# OLED_0_96-inch_Sch.net
KiCad netlist of a schematic drawn in Altium Designer
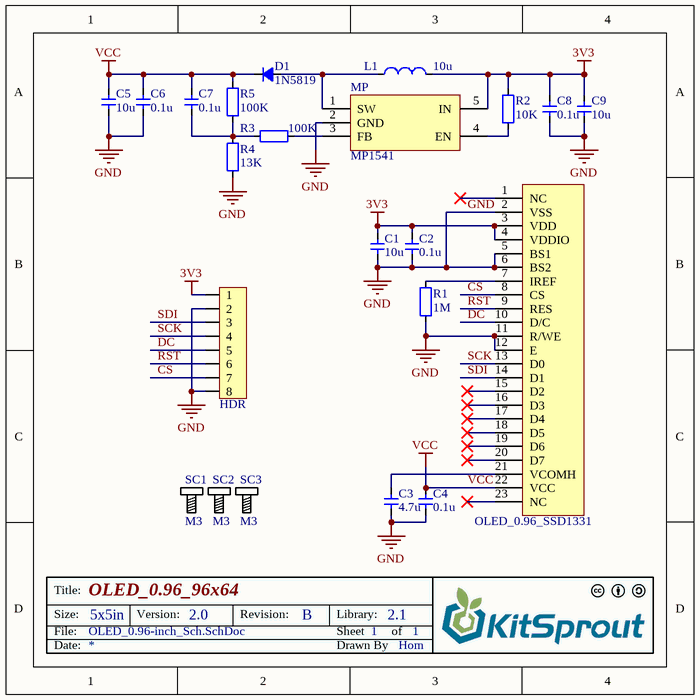
[diagram p0: OLED_0.96-inch_Sch.SchDoc]

(export (version "E")
  (design (tool "Eeschema 10.0.6"))
  (components
    (comp (ref "C1")
      (value "10u")
      (footprint "PCB_PassiveCap:CAP_0805")
      (description "Capacitor")
      (fields (field (name "Comment") "Cap_0805"))
      (libsource (lib "SCH_Passive") (part "Cap_0805"))
    )
    (comp (ref "C2")
      (value "0.1u")
      (footprint "PCB_PassiveCap:CAP_0805")
      (description "Capacitor")
      (fields (field (name "Comment") "Cap_0805"))
      (libsource (lib "SCH_Passive") (part "Cap_0805"))
    )
    (comp (ref "C3")
      (value "4.7u")
      (footprint "PCB_PassiveCap:CAP_0805")
      (description "Capacitor")
      (fields (field (name "Comment") "Cap_0805"))
      (libsource (lib "SCH_Passive") (part "Cap_0805"))
    )
    (comp (ref "C4")
      (value "0.1u")
      (footprint "PCB_PassiveCap:CAP_0805")
      (description "Capacitor")
      (fields (field (name "Comment") "Cap_0805"))
      (libsource (lib "SCH_Passive") (part "Cap_0805"))
    )
    (comp (ref "C5")
      (value "10u")
      (footprint "PCB_PassiveCap:CAP_0805")
      (description "Capacitor")
      (fields (field (name "Comment") "Cap_0805"))
      (libsource (lib "SCH_Passive") (part "Cap_0805"))
    )
    (comp (ref "C6")
      (value "0.1u")
      (footprint "PCB_PassiveCap:CAP_0805")
      (description "Capacitor")
      (fields (field (name "Comment") "Cap_0805"))
      (libsource (lib "SCH_Passive") (part "Cap_0805"))
    )
    (comp (ref "C7")
      (value "0.1u")
      (footprint "PCB_PassiveCap:CAP_0805")
      (description "Capacitor")
      (fields (field (name "Comment") "Cap_0805"))
      (libsource (lib "SCH_Passive") (part "Cap_0805"))
    )
    (comp (ref "C8")
      (value "0.1u")
      (footprint "PCB_PassiveCap:CAP_0805")
      (description "Capacitor")
      (fields (field (name "Comment") "Cap_0805"))
      (libsource (lib "SCH_Passive") (part "Cap_0805"))
    )
    (comp (ref "C9")
      (value "10u")
      (footprint "PCB_PassiveCap:CAP_0805")
      (description "Capacitor")
      (fields (field (name "Comment") "Cap_0805"))
      (libsource (lib "SCH_Passive") (part "Cap_0805"))
    )
    (comp (ref "D1")
      (value "1N5819")
      (footprint "PCB_ActiveDIO:DO-214AC")
      (description "Diode")
      (fields (field (name "Comment") "Diode_SMA"))
      (libsource (lib "SCH_Active") (part "Diode_SMA"))
    )
    (comp (ref "HDR")
      (value "HDR1x8_1.27")
      (footprint "PCB_ConnectorHDR:HDR1X8_1.27_180")
      (description "Header")
      (libsource (lib "SCH_ConnectorHDR") (part "HDR1x8_1.27"))
    )
    (comp (ref "L1")
      (value "10u")
      (footprint "PCB_PassiveInd:IND_CD32")
      (description "Inductor")
      (fields (field (name "Comment") "Ind_CD32"))
      (libsource (lib "SCH_Passive") (part "Ind_CD32"))
    )
    (comp (ref "MP")
      (value "MP1541")
      (footprint "PCB_IntegratedCircuit:SOT23-5")
      (description "Boost")
      (libsource (lib "SCH_IntegratedCircuit") (part "MP1541"))
    )
    (comp (ref "OLED_0.96_SSD1331")
      (value "OLED_0.96_SSD1331")
      (footprint "PCB_Module:OLED_0.96_96x64_SSD1331")
      (description "OLED")
      (libsource (lib "SCH_Module") (part "OLED_0.96_SSD1331"))
    )
    (comp (ref "R1")
      (value "1M")
      (footprint "PCB_PassiveRes:RES_0603")
      (description "Resistor")
      (fields (field (name "Comment") "Res_0603"))
      (libsource (lib "SCH_Passive") (part "Res_0603"))
    )
    (comp (ref "R2")
      (value "10K")
      (footprint "PCB_PassiveRes:RES_0603")
      (description "Resistor")
      (fields (field (name "Comment") "Res_0603"))
      (libsource (lib "SCH_Passive") (part "Res_0603"))
    )
    (comp (ref "R3")
      (value "100K")
      (footprint "PCB_PassiveRes:RES_0603")
      (description "Resistor")
      (fields (field (name "Comment") "Res_0603"))
      (libsource (lib "") (part "Res_0603_1"))
    )
    (comp (ref "R4")
      (value "13K")
      (footprint "PCB_PassiveRes:RES_0603")
      (description "Resistor")
      (fields (field (name "Comment") "Res_0603"))
      (libsource (lib "SCH_Passive") (part "Res_0603"))
    )
    (comp (ref "R5")
      (value "100K")
      (footprint "PCB_PassiveRes:RES_0603")
      (description "Resistor")
      (fields (field (name "Comment") "Res_0603"))
      (libsource (lib "SCH_Passive") (part "Res_0603"))
    )
    (comp (ref "SC1")
      (value "M3")
      (footprint "PCB_Mechanical:SCRREW_M3")
      (description "Screw")
      (libsource (lib "SCH_Mechanical") (part "Screw_M3"))
    )
    (comp (ref "SC2")
      (value "M3")
      (footprint "PCB_Mechanical:SCRREW_M3")
      (description "Screw")
      (libsource (lib "SCH_Mechanical") (part "Screw_M3"))
    )
    (comp (ref "SC3")
      (value "M3")
      (footprint "PCB_Mechanical:SCRREW_M3")
      (description "Screw")
      (libsource (lib "SCH_Mechanical") (part "Screw_M3"))
    )
  )
  (nets
    (net (code "1") (name "/CS") (class "Default")
      (node (ref "HDR") (pin "7") (pinfunction "7_7") (pintype "passive"))
      (node (ref "OLED_0.96_SSD1331") (pin "8") (pinfunction "CS_8") (pintype "passive"))
    )
    (net (code "2") (name "/DC") (class "Default")
      (node (ref "HDR") (pin "5") (pinfunction "5_5") (pintype "passive"))
      (node (ref "OLED_0.96_SSD1331") (pin "10") (pinfunction "D/C_10") (pintype "passive"))
    )
    (net (code "3") (name "/RST") (class "Default")
      (node (ref "HDR") (pin "6") (pinfunction "6_6") (pintype "passive"))
      (node (ref "OLED_0.96_SSD1331") (pin "9") (pinfunction "RES_9") (pintype "passive"))
    )
    (net (code "4") (name "/SCK") (class "Default")
      (node (ref "HDR") (pin "4") (pinfunction "4_4") (pintype "passive"))
      (node (ref "OLED_0.96_SSD1331") (pin "13") (pinfunction "D0_13") (pintype "passive"))
    )
    (net (code "5") (name "/SDI") (class "Default")
      (node (ref "HDR") (pin "3") (pinfunction "3_3") (pintype "passive"))
      (node (ref "OLED_0.96_SSD1331") (pin "14") (pinfunction "D1_14") (pintype "passive"))
    )
    (net (code "6") (name "3V3") (class "Default")
      (node (ref "C1") (pin "2") (pinfunction "2_2") (pintype "passive"))
      (node (ref "C2") (pin "2") (pinfunction "2_2") (pintype "passive"))
      (node (ref "C8") (pin "2") (pinfunction "2_2") (pintype "passive"))
      (node (ref "C9") (pin "2") (pinfunction "2_2") (pintype "passive"))
      (node (ref "HDR") (pin "1") (pinfunction "1_1") (pintype "passive"))
      (node (ref "L1") (pin "2") (pinfunction "2_2") (pintype "passive"))
      (node (ref "MP") (pin "5") (pinfunction "IN_5") (pintype "passive"))
      (node (ref "OLED_0.96_SSD1331") (pin "3") (pinfunction "VDD_3") (pintype "passive"))
      (node (ref "OLED_0.96_SSD1331") (pin "4") (pinfunction "VDDIO_4") (pintype "passive"))
      (node (ref "R2") (pin "2") (pinfunction "2_2") (pintype "passive"))
    )
    (net (code "7") (name "GND") (class "Default")
      (node (ref "C1") (pin "1") (pinfunction "1_1") (pintype "passive"))
      (node (ref "C2") (pin "1") (pinfunction "1_1") (pintype "passive"))
      (node (ref "C3") (pin "1") (pinfunction "1_1") (pintype "passive"))
      (node (ref "C4") (pin "1") (pinfunction "1_1") (pintype "passive"))
      (node (ref "C5") (pin "1") (pinfunction "1_1") (pintype "passive"))
      (node (ref "C6") (pin "1") (pinfunction "1_1") (pintype "passive"))
      (node (ref "C8") (pin "1") (pinfunction "1_1") (pintype "passive"))
      (node (ref "C9") (pin "1") (pinfunction "1_1") (pintype "passive"))
      (node (ref "HDR") (pin "2") (pinfunction "2_2") (pintype "passive"))
      (node (ref "HDR") (pin "8") (pinfunction "8_8") (pintype "passive"))
      (node (ref "MP") (pin "2") (pinfunction "GND_2") (pintype "passive"))
      (node (ref "OLED_0.96_SSD1331") (pin "11") (pinfunction "R/WE_11") (pintype "passive"))
      (node (ref "OLED_0.96_SSD1331") (pin "12") (pinfunction "E_12") (pintype "passive"))
      (node (ref "OLED_0.96_SSD1331") (pin "2") (pinfunction "VSS_2") (pintype "passive"))
      (node (ref "OLED_0.96_SSD1331") (pin "5") (pinfunction "BS1_5") (pintype "passive"))
      (node (ref "OLED_0.96_SSD1331") (pin "6") (pinfunction "BS2_6") (pintype "passive"))
      (node (ref "R1") (pin "1") (pinfunction "1_1") (pintype "passive"))
      (node (ref "R4") (pin "1") (pinfunction "1_1") (pintype "passive"))
    )
    (net (code "8") (name "Net-(C7-Pad1)") (class "Default")
      (node (ref "C7") (pin "1") (pinfunction "1_1") (pintype "passive"))
      (node (ref "R3") (pin "2") (pinfunction "2_2") (pintype "passive"))
      (node (ref "R4") (pin "2") (pinfunction "2_2") (pintype "passive"))
      (node (ref "R5") (pin "1") (pinfunction "1_1") (pintype "passive"))
    )
    (net (code "9") (name "Net-(D1-A)") (class "Default")
      (node (ref "D1") (pin "1") (pinfunction "A_1") (pintype "passive"))
      (node (ref "L1") (pin "1") (pinfunction "1_1") (pintype "passive"))
      (node (ref "MP") (pin "1") (pinfunction "SW_1") (pintype "passive"))
    )
    (net (code "10") (name "Net-(MP-EN)") (class "Default")
      (node (ref "MP") (pin "4") (pinfunction "EN_4") (pintype "passive"))
      (node (ref "R2") (pin "1") (pinfunction "1_1") (pintype "passive"))
    )
    (net (code "11") (name "Net-(MP-FB)") (class "Default")
      (node (ref "MP") (pin "3") (pinfunction "FB_3") (pintype "passive"))
      (node (ref "R3") (pin "1") (pinfunction "1_1") (pintype "passive"))
    )
    (net (code "12") (name "Net-(OLED_0.96_SSD1331-IREF)") (class "Default")
      (node (ref "OLED_0.96_SSD1331") (pin "7") (pinfunction "IREF_7") (pintype "passive"))
      (node (ref "R1") (pin "2") (pinfunction "2_2") (pintype "passive"))
    )
    (net (code "13") (name "Net-(OLED_0.96_SSD1331-VCOMH)") (class "Default")
      (node (ref "C3") (pin "2") (pinfunction "2_2") (pintype "passive"))
      (node (ref "OLED_0.96_SSD1331") (pin "21") (pinfunction "VCOMH_21") (pintype "passive"))
    )
    (net (code "14") (name "VCC") (class "Default")
      (node (ref "C4") (pin "2") (pinfunction "2_2") (pintype "passive"))
      (node (ref "C5") (pin "2") (pinfunction "2_2") (pintype "passive"))
      (node (ref "C6") (pin "2") (pinfunction "2_2") (pintype "passive"))
      (node (ref "C7") (pin "2") (pinfunction "2_2") (pintype "passive"))
      (node (ref "D1") (pin "2") (pinfunction "K_2") (pintype "passive"))
      (node (ref "OLED_0.96_SSD1331") (pin "22") (pinfunction "VCC_22") (pintype "passive"))
      (node (ref "R5") (pin "2") (pinfunction "2_2") (pintype "passive"))
    )
    (net (code "15") (name "unconnected-(OLED_0.96_SSD1331-D2-Pad15)") (class "Default")
      (node (ref "OLED_0.96_SSD1331") (pin "15") (pinfunction "D2_15") (pintype "passive+no_connect"))
    )
    (net (code "16") (name "unconnected-(OLED_0.96_SSD1331-D3-Pad16)") (class "Default")
      (node (ref "OLED_0.96_SSD1331") (pin "16") (pinfunction "D3_16") (pintype "passive+no_connect"))
    )
    (net (code "17") (name "unconnected-(OLED_0.96_SSD1331-D4-Pad17)") (class "Default")
      (node (ref "OLED_0.96_SSD1331") (pin "17") (pinfunction "D4_17") (pintype "passive+no_connect"))
    )
    (net (code "18") (name "unconnected-(OLED_0.96_SSD1331-D5-Pad18)") (class "Default")
      (node (ref "OLED_0.96_SSD1331") (pin "18") (pinfunction "D5_18") (pintype "passive+no_connect"))
    )
    (net (code "19") (name "unconnected-(OLED_0.96_SSD1331-D6-Pad19)") (class "Default")
      (node (ref "OLED_0.96_SSD1331") (pin "19") (pinfunction "D6_19") (pintype "passive+no_connect"))
    )
    (net (code "20") (name "unconnected-(OLED_0.96_SSD1331-D7-Pad20)") (class "Default")
      (node (ref "OLED_0.96_SSD1331") (pin "20") (pinfunction "D7_20") (pintype "passive+no_connect"))
    )
    (net (code "21") (name "unconnected-(OLED_0.96_SSD1331-NC-Pad1)") (class "Default")
      (node (ref "OLED_0.96_SSD1331") (pin "1") (pinfunction "NC_1") (pintype "passive+no_connect"))
    )
    (net (code "22") (name "unconnected-(OLED_0.96_SSD1331-NC-Pad23)") (class "Default")
      (node (ref "OLED_0.96_SSD1331") (pin "23") (pinfunction "NC_23") (pintype "passive+no_connect"))
    )
  )
)
